# Power_Supply.net
KiCad netlist of a schematic drawn in Altium Designer
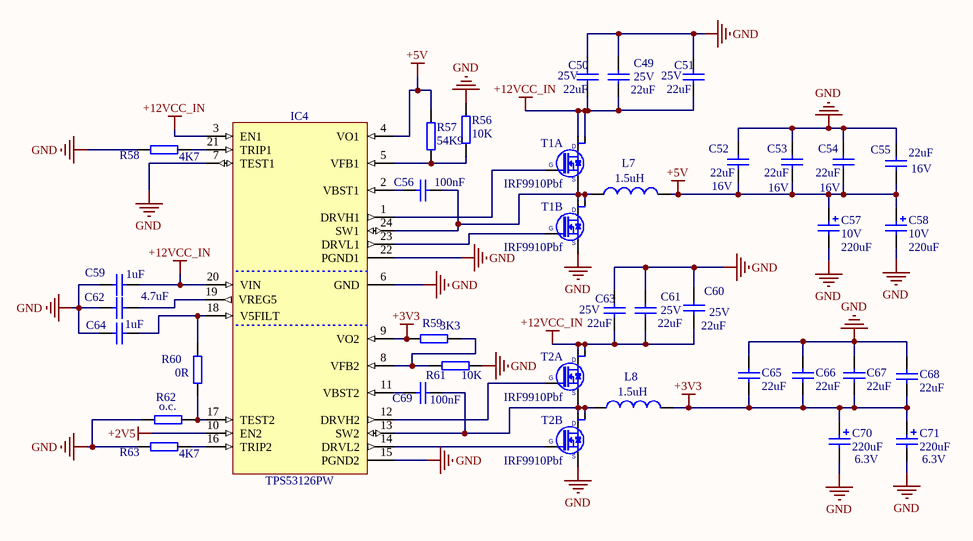
[diagram p0: Power_Supply.SchDoc]

(export (version "E")
  (design (tool "Eeschema 10.0.6"))
  (components
    (comp (ref "C49")
      (value "22uF")
      (footprint "CC3216-1206")
      (description "Capacitor")
      (fields
        (field (name "TOLERANCE") "±10%")
        (field (name "VOLTAGE") "25V")
        (field (name "Comment") "22uF 25V")
        (field (name "PUBLISHER") "Altium Limited")
      )
      (libsource (lib "wr_switch") (part "Cap"))
    )
    (comp (ref "C50")
      (value "22uF")
      (footprint "CC3216-1206")
      (description "Capacitor")
      (fields
        (field (name "TOLERANCE") "±10%")
        (field (name "VOLTAGE") "25V")
        (field (name "Comment") "22uF 25V")
        (field (name "PUBLISHER") "Altium Limited")
      )
      (libsource (lib "wr_switch") (part "Cap"))
    )
    (comp (ref "C51")
      (value "22uF")
      (footprint "CC3216-1206")
      (description "Capacitor")
      (fields
        (field (name "TOLERANCE") "±10%")
        (field (name "VOLTAGE") "25V")
        (field (name "Comment") "22uF 25V")
        (field (name "PUBLISHER") "Altium Limited")
      )
      (libsource (lib "wr_switch") (part "Cap"))
    )
    (comp (ref "C52")
      (value "22uF")
      (footprint "CC2012-0805")
      (description "Capacitor")
      (fields
        (field (name "TOLERANCE") "±10%")
        (field (name "VOLTAGE") "16V")
        (field (name "Comment") "22uF 16V")
        (field (name "PUBLISHER") "Altium Limited")
      )
      (libsource (lib "wr_switch") (part "Cap"))
    )
    (comp (ref "C53")
      (value "22uF")
      (footprint "CC2012-0805")
      (description "Capacitor")
      (fields
        (field (name "TOLERANCE") "±10%")
        (field (name "VOLTAGE") "16V")
        (field (name "Comment") "22uF 16V")
        (field (name "PUBLISHER") "Altium Limited")
      )
      (libsource (lib "wr_switch") (part "Cap"))
    )
    (comp (ref "C54")
      (value "22uF")
      (footprint "CC2012-0805")
      (description "Capacitor")
      (fields
        (field (name "TOLERANCE") "±10%")
        (field (name "VOLTAGE") "16V")
        (field (name "Comment") "22uF 16V")
        (field (name "PUBLISHER") "Altium Limited")
      )
      (libsource (lib "wr_switch") (part "Cap"))
    )
    (comp (ref "C55")
      (value "22uF")
      (footprint "CC2012-0805")
      (description "Capacitor")
      (fields
        (field (name "TOLERANCE") "±10%")
        (field (name "VOLTAGE") "16V")
        (field (name "Comment") "22uF 16V")
        (field (name "PUBLISHER") "Altium Limited")
      )
      (libsource (lib "wr_switch") (part "Cap"))
    )
    (comp (ref "C56")
      (value "100nF")
      (footprint "CC1005-0402")
      (description "Capacitor")
      (fields
        (field (name "TOLERANCE") "±10%")
        (field (name "VOLTAGE") "16V")
        (field (name "PUBLISHER") "Altium Limited")
      )
      (libsource (lib "wr_switch") (part "Cap"))
    )
    (comp (ref "C57")
      (value "220uF")
      (footprint "D")
      (description "Polarized Capacitor Tantalum")
      (fields
        (field (name "TOLERANCE") "±20%")
        (field (name "VOLTAGE") "10V")
        (field (name "Comment") "220uF 10V")
        (field (name "PUBLISHER") "Altium Limited")
      )
      (libsource (lib "wr_switch") (part "Cap Pol1"))
    )
    (comp (ref "C58")
      (value "220uF")
      (footprint "D")
      (description "Polarized Capacitor Tantalum")
      (fields
        (field (name "TOLERANCE") "±20%")
        (field (name "VOLTAGE") "10V")
        (field (name "Comment") "220uF 10V")
        (field (name "PUBLISHER") "Altium Limited")
      )
      (libsource (lib "wr_switch") (part "Cap Pol1"))
    )
    (comp (ref "C59")
      (value "1uF")
      (footprint "CC1608-0603")
      (description "Capacitor")
      (fields
        (field (name "TOLERANCE") "±10%")
        (field (name "VOLTAGE") "25V")
        (field (name "PUBLISHER") "Altium Limited")
      )
      (libsource (lib "wr_switch") (part "Cap"))
    )
    (comp (ref "C60")
      (value "22uF")
      (footprint "CC3216-1206")
      (description "Capacitor")
      (fields
        (field (name "TOLERANCE") "±10%")
        (field (name "VOLTAGE") "25V")
        (field (name "Comment") "22uF 25V")
        (field (name "PUBLISHER") "Altium Limited")
      )
      (libsource (lib "wr_switch") (part "Cap"))
    )
    (comp (ref "C61")
      (value "22uF")
      (footprint "CC3216-1206")
      (description "Capacitor")
      (fields
        (field (name "TOLERANCE") "±10%")
        (field (name "VOLTAGE") "25V")
        (field (name "Comment") "22uF 25V")
        (field (name "PUBLISHER") "Altium Limited")
      )
      (libsource (lib "wr_switch") (part "Cap"))
    )
    (comp (ref "C62")
      (value "4.7uF")
      (footprint "CC1608-0603")
      (description "Capacitor")
      (fields
        (field (name "TOLERANCE") "±10%")
        (field (name "VOLTAGE") "10V")
        (field (name "PUBLISHER") "Altium Limited")
      )
      (libsource (lib "wr_switch") (part "Cap"))
    )
    (comp (ref "C63")
      (value "22uF")
      (footprint "CC3216-1206")
      (description "Capacitor")
      (fields
        (field (name "TOLERANCE") "±10%")
        (field (name "VOLTAGE") "25V")
        (field (name "Comment") "22uF 25V")
        (field (name "PUBLISHER") "Altium Limited")
      )
      (libsource (lib "wr_switch") (part "Cap"))
    )
    (comp (ref "C64")
      (value "1uF")
      (footprint "CC1005-0402")
      (description "Capacitor")
      (fields
        (field (name "TOLERANCE") "±10%")
        (field (name "VOLTAGE") "16V")
        (field (name "PUBLISHER") "Altium Limited")
      )
      (libsource (lib "wr_switch") (part "Cap"))
    )
    (comp (ref "C65")
      (value "22uF")
      (footprint "CC2012-0805")
      (description "Capacitor")
      (fields
        (field (name "TOLERANCE") "±20%")
        (field (name "VOLTAGE") "6.3V")
        (field (name "PUBLISHER") "Altium Limited")
      )
      (libsource (lib "wr_switch") (part "Cap"))
    )
    (comp (ref "C66")
      (value "22uF")
      (footprint "CC2012-0805")
      (description "Capacitor")
      (fields
        (field (name "TOLERANCE") "±20%")
        (field (name "VOLTAGE") "6.3V")
        (field (name "PUBLISHER") "Altium Limited")
      )
      (libsource (lib "wr_switch") (part "Cap"))
    )
    (comp (ref "C67")
      (value "22uF")
      (footprint "CC2012-0805")
      (description "Capacitor")
      (fields
        (field (name "TOLERANCE") "±20%")
        (field (name "VOLTAGE") "6.3V")
        (field (name "PUBLISHER") "Altium Limited")
      )
      (libsource (lib "wr_switch") (part "Cap"))
    )
    (comp (ref "C68")
      (value "22uF")
      (footprint "CC2012-0805")
      (description "Capacitor")
      (fields
        (field (name "TOLERANCE") "±20%")
        (field (name "VOLTAGE") "6.3V")
        (field (name "PUBLISHER") "Altium Limited")
      )
      (libsource (lib "wr_switch") (part "Cap"))
    )
    (comp (ref "C69")
      (value "100nF")
      (footprint "CC1005-0402")
      (description "Capacitor")
      (fields
        (field (name "TOLERANCE") "±10%")
        (field (name "VOLTAGE") "16V")
        (field (name "PUBLISHER") "Altium Limited")
      )
      (libsource (lib "wr_switch") (part "Cap"))
    )
    (comp (ref "C70")
      (value "220uF")
      (footprint "D")
      (description "Polarized Capacitor Tantalum")
      (fields
        (field (name "TOLERANCE") "±20%")
        (field (name "VOLTAGE") "6.3V")
        (field (name "PUBLISHER") "Altium Limited")
      )
      (libsource (lib "wr_switch") (part "Cap Pol1"))
    )
    (comp (ref "C71")
      (value "220uF")
      (footprint "D")
      (description "Polarized Capacitor Tantalum")
      (fields
        (field (name "TOLERANCE") "±20%")
        (field (name "VOLTAGE") "6.3V")
        (field (name "PUBLISHER") "Altium Limited")
      )
      (libsource (lib "wr_switch") (part "Cap Pol1"))
    )
    (comp (ref "IC4")
      (value "TPS53126PW")
      (footprint "SOP65P640X120-24N")
      (description "Dual Synchronous Step-Down Controller For Low Voltage Power Rails")
      (fields (field (name "MANUFACTURER") "TEXAS INSTRUMENTS") (field (name "AUTHOR") "CERN DEM JLC"))
      (libsource (lib "wr_switch") (part "TPS53126PW"))
    )
    (comp (ref "L7")
      (value "1.5uH")
      (footprint "IHLP2525")
      (description "Low Profile, High Current Inductor")
      (fields
        (field (name "MANUFACTURER") "Vishay/Dale")
        (field (name "Comment") "IHLP2525CZER1R5M01")
        (field (name "PUBLISHER") "Altium Limited")
      )
      (libsource (lib "Miscellaneous Devices") (part "Inductor"))
    )
    (comp (ref "L8")
      (value "1.5uH")
      (footprint "IHLP2525")
      (description "Low Profile, High Current Inductor")
      (fields
        (field (name "MANUFACTURER") "Vishay/Dale")
        (field (name "Comment") "IHLP2525CZER1R5M01")
        (field (name "PUBLISHER") "Altium Limited")
      )
      (libsource (lib "Miscellaneous Devices") (part "Inductor"))
    )
    (comp (ref "R56")
      (value "10K")
      (footprint "0402")
      (description "SMD Resistor")
      (fields (field (name "TOLERANCE") "±1%"))
      (libsource (lib "wr_switch") (part "RES_SMD"))
    )
    (comp (ref "R57")
      (value "54K9")
      (footprint "0603")
      (description "SMD Resistor")
      (fields (field (name "TOLERANCE") "±1%"))
      (libsource (lib "wr_switch") (part "RES_SMD"))
    )
    (comp (ref "R58")
      (value "4K7")
      (footprint "0402")
      (description "SMD Resistor")
      (fields (field (name "TOLERANCE") "±1%"))
      (libsource (lib "wr_switch") (part "RES_SMD"))
    )
    (comp (ref "R59")
      (value "3K3")
      (footprint "0603")
      (description "SMD Resistor")
      (fields (field (name "TOLERANCE") "±1%"))
      (libsource (lib "wr_switch") (part "RES_SMD"))
    )
    (comp (ref "R60")
      (value "0R")
      (footprint "0402")
      (description "SMD Resistor")
      (fields (field (name "TOLERANCE") "Jumper"))
      (libsource (lib "wr_switch") (part "RES_SMD"))
    )
    (comp (ref "R61")
      (value "10K")
      (footprint "0402")
      (description "SMD Resistor")
      (fields (field (name "TOLERANCE") "±1%"))
      (libsource (lib "wr_switch") (part "RES_SMD"))
    )
    (comp (ref "R62")
      (value "o.c.")
      (footprint "0402")
      (description "SMD Resistor")
      (libsource (lib "wr_switch") (part "RES_SMD"))
    )
    (comp (ref "R63")
      (value "4K7")
      (footprint "0402")
      (description "SMD Resistor")
      (fields (field (name "TOLERANCE") "±1%"))
      (libsource (lib "wr_switch") (part "RES_SMD"))
    )
    (comp (ref "T1")
      (value "IRF9910Pbf")
      (footprint "SOIC127P600X175-8N")
      (description "Dual SO-8 MOSFET For POL Cconverter")
      (fields (field (name "MANUFACTURER") "INTERNATIONAL RECTIFIER") (field (name "AUTHOR") "CERN DEM JLC"))
      (libsource (lib "ICs And Semiconductors") (part "IRF9910"))
    )
    (comp (ref "T2")
      (value "IRF9910Pbf")
      (footprint "SOIC127P600X175-8N")
      (description "Dual SO-8 MOSFET For POL Cconverter")
      (fields (field (name "MANUFACTURER") "INTERNATIONAL RECTIFIER") (field (name "AUTHOR") "CERN DEM JLC"))
      (libsource (lib "ICs And Semiconductors") (part "IRF9910"))
    )
  )
  (nets
    (net (code "1") (name "+2V5") (class "Default")
      (node (ref "IC4") (pin "10") (pinfunction "EN2_10") (pintype "input"))
    )
    (net (code "2") (name "+3V3") (class "Default")
      (node (ref "C65") (pin "2") (pinfunction "2_2") (pintype "passive"))
      (node (ref "C66") (pin "1") (pinfunction "1_1") (pintype "passive"))
      (node (ref "C67") (pin "1") (pinfunction "1_1") (pintype "passive"))
      (node (ref "C68") (pin "1") (pinfunction "1_1") (pintype "passive"))
      (node (ref "C70") (pin "1") (pinfunction "1_1") (pintype "passive"))
      (node (ref "C71") (pin "1") (pinfunction "1_1") (pintype "passive"))
      (node (ref "IC4") (pin "9") (pinfunction "VO2_9") (pintype "input"))
      (node (ref "L8") (pin "2") (pinfunction "2_2") (pintype "passive"))
      (node (ref "R59") (pin "1") (pinfunction "1_1") (pintype "passive"))
    )
    (net (code "3") (name "+5V") (class "Default")
      (node (ref "C52") (pin "1") (pinfunction "1_1") (pintype "passive"))
      (node (ref "C53") (pin "1") (pinfunction "1_1") (pintype "passive"))
      (node (ref "C54") (pin "1") (pinfunction "1_1") (pintype "passive"))
      (node (ref "C55") (pin "1") (pinfunction "1_1") (pintype "passive"))
      (node (ref "C57") (pin "1") (pinfunction "1_1") (pintype "passive"))
      (node (ref "C58") (pin "1") (pinfunction "1_1") (pintype "passive"))
      (node (ref "IC4") (pin "4") (pinfunction "VO1_4") (pintype "input"))
      (node (ref "L7") (pin "2") (pinfunction "2_2") (pintype "passive"))
      (node (ref "R57") (pin "2") (pinfunction "2_2") (pintype "passive"))
    )
    (net (code "4") (name "+12VCC_IN") (class "Default")
      (node (ref "C49") (pin "1") (pinfunction "1_1") (pintype "passive"))
      (node (ref "C50") (pin "1") (pinfunction "1_1") (pintype "passive"))
      (node (ref "C51") (pin "1") (pinfunction "1_1") (pintype "passive"))
      (node (ref "C59") (pin "2") (pinfunction "2_2") (pintype "passive"))
      (node (ref "C60") (pin "1") (pinfunction "1_1") (pintype "passive"))
      (node (ref "C61") (pin "1") (pinfunction "1_1") (pintype "passive"))
      (node (ref "C63") (pin "1") (pinfunction "1_1") (pintype "passive"))
      (node (ref "IC4") (pin "20") (pinfunction "VIN_20") (pintype "input"))
      (node (ref "IC4") (pin "3") (pinfunction "EN1_3") (pintype "input"))
      (node (ref "T1") (pin "5") (pinfunction "D_5") (pintype "passive"))
      (node (ref "T1") (pin "6") (pinfunction "D_6") (pintype "passive"))
      (node (ref "T2") (pin "5") (pinfunction "D_5") (pintype "passive"))
      (node (ref "T2") (pin "6") (pinfunction "D_6") (pintype "passive"))
    )
    (net (code "5") (name "GND") (class "Default")
      (node (ref "C49") (pin "2") (pinfunction "2_2") (pintype "passive"))
      (node (ref "C50") (pin "2") (pinfunction "2_2") (pintype "passive"))
      (node (ref "C51") (pin "2") (pinfunction "2_2") (pintype "passive"))
      (node (ref "C52") (pin "2") (pinfunction "2_2") (pintype "passive"))
      (node (ref "C53") (pin "2") (pinfunction "2_2") (pintype "passive"))
      (node (ref "C54") (pin "2") (pinfunction "2_2") (pintype "passive"))
      (node (ref "C55") (pin "2") (pinfunction "2_2") (pintype "passive"))
      (node (ref "C57") (pin "2") (pinfunction "2_2") (pintype "passive"))
      (node (ref "C58") (pin "2") (pinfunction "2_2") (pintype "passive"))
      (node (ref "C59") (pin "1") (pinfunction "1_1") (pintype "passive"))
      (node (ref "C60") (pin "2") (pinfunction "2_2") (pintype "passive"))
      (node (ref "C61") (pin "2") (pinfunction "2_2") (pintype "passive"))
      (node (ref "C62") (pin "2") (pinfunction "2_2") (pintype "passive"))
      (node (ref "C63") (pin "2") (pinfunction "2_2") (pintype "passive"))
      (node (ref "C64") (pin "1") (pinfunction "1_1") (pintype "passive"))
      (node (ref "C65") (pin "1") (pinfunction "1_1") (pintype "passive"))
      (node (ref "C66") (pin "2") (pinfunction "2_2") (pintype "passive"))
      (node (ref "C67") (pin "2") (pinfunction "2_2") (pintype "passive"))
      (node (ref "C68") (pin "2") (pinfunction "2_2") (pintype "passive"))
      (node (ref "C70") (pin "2") (pinfunction "2_2") (pintype "passive"))
      (node (ref "C71") (pin "2") (pinfunction "2_2") (pintype "passive"))
      (node (ref "IC4") (pin "15") (pinfunction "PGND2_15") (pintype "power_in"))
      (node (ref "IC4") (pin "22") (pinfunction "PGND1_22") (pintype "power_in"))
      (node (ref "IC4") (pin "6") (pinfunction "GND_6") (pintype "power_in"))
      (node (ref "IC4") (pin "7") (pinfunction "TEST1_7") (pintype "bidirectional"))
      (node (ref "R56") (pin "2") (pinfunction "2_2") (pintype "passive"))
      (node (ref "R58") (pin "2") (pinfunction "2_2") (pintype "passive"))
      (node (ref "R61") (pin "2") (pinfunction "2_2") (pintype "passive"))
      (node (ref "R62") (pin "1") (pinfunction "1_1") (pintype "passive"))
      (node (ref "R63") (pin "2") (pinfunction "2_2") (pintype "passive"))
      (node (ref "T1") (pin "1") (pinfunction "S_1") (pintype "passive"))
      (node (ref "T2") (pin "1") (pinfunction "S_1") (pintype "passive"))
    )
    (net (code "6") (name "Net-(IC4-DRVH1)") (class "Default")
      (node (ref "IC4") (pin "1") (pinfunction "DRVH1_1") (pintype "output"))
      (node (ref "T1") (pin "4") (pinfunction "G_4") (pintype "passive"))
    )
    (net (code "7") (name "Net-(IC4-DRVH2)") (class "Default")
      (node (ref "IC4") (pin "12") (pinfunction "DRVH2_12") (pintype "output"))
      (node (ref "T2") (pin "4") (pinfunction "G_4") (pintype "passive"))
    )
    (net (code "8") (name "Net-(IC4-DRVL1)") (class "Default")
      (node (ref "IC4") (pin "23") (pinfunction "DRVL1_23") (pintype "output"))
      (node (ref "T1") (pin "2") (pinfunction "G_2") (pintype "passive"))
    )
    (net (code "9") (name "Net-(IC4-DRVL2)") (class "Default")
      (node (ref "IC4") (pin "14") (pinfunction "DRVL2_14") (pintype "output"))
      (node (ref "T2") (pin "2") (pinfunction "G_2") (pintype "passive"))
    )
    (net (code "10") (name "Net-(IC4-SW1)") (class "Default")
      (node (ref "C56") (pin "2") (pinfunction "2_2") (pintype "passive"))
      (node (ref "IC4") (pin "24") (pinfunction "SW1_24") (pintype "bidirectional"))
      (node (ref "L7") (pin "1") (pinfunction "1_1") (pintype "passive"))
      (node (ref "T1") (pin "3") (pinfunction "S_3") (pintype "passive"))
      (node (ref "T1") (pin "7") (pinfunction "D_7") (pintype "passive"))
      (node (ref "T1") (pin "8") (pinfunction "D_8") (pintype "passive"))
    )
    (net (code "11") (name "Net-(IC4-SW2)") (class "Default")
      (node (ref "C69") (pin "2") (pinfunction "2_2") (pintype "passive"))
      (node (ref "IC4") (pin "13") (pinfunction "SW2_13") (pintype "bidirectional"))
      (node (ref "L8") (pin "1") (pinfunction "1_1") (pintype "passive"))
      (node (ref "T2") (pin "3") (pinfunction "S_3") (pintype "passive"))
      (node (ref "T2") (pin "7") (pinfunction "D_7") (pintype "passive"))
      (node (ref "T2") (pin "8") (pinfunction "D_8") (pintype "passive"))
    )
    (net (code "12") (name "Net-(IC4-TEST2)") (class "Default")
      (node (ref "IC4") (pin "17") (pinfunction "TEST2_17") (pintype "input"))
      (node (ref "R60") (pin "2") (pinfunction "2_2") (pintype "passive"))
      (node (ref "R62") (pin "2") (pinfunction "2_2") (pintype "passive"))
    )
    (net (code "13") (name "Net-(IC4-TRIP1)") (class "Default")
      (node (ref "IC4") (pin "21") (pinfunction "TRIP1_21") (pintype "input"))
      (node (ref "R58") (pin "1") (pinfunction "1_1") (pintype "passive"))
    )
    (net (code "14") (name "Net-(IC4-TRIP2)") (class "Default")
      (node (ref "IC4") (pin "16") (pinfunction "TRIP2_16") (pintype "input"))
      (node (ref "R63") (pin "1") (pinfunction "1_1") (pintype "passive"))
    )
    (net (code "15") (name "Net-(IC4-V5FILT)") (class "Default")
      (node (ref "C64") (pin "2") (pinfunction "2_2") (pintype "passive"))
      (node (ref "IC4") (pin "18") (pinfunction "V5FILT_18") (pintype "input"))
      (node (ref "R60") (pin "1") (pinfunction "1_1") (pintype "passive"))
    )
    (net (code "16") (name "Net-(IC4-VBST1)") (class "Default")
      (node (ref "C56") (pin "1") (pinfunction "1_1") (pintype "passive"))
      (node (ref "IC4") (pin "2") (pinfunction "VBST1_2") (pintype "input"))
    )
    (net (code "17") (name "Net-(IC4-VBST2)") (class "Default")
      (node (ref "C69") (pin "1") (pinfunction "1_1") (pintype "passive"))
      (node (ref "IC4") (pin "11") (pinfunction "VBST2_11") (pintype "input"))
    )
    (net (code "18") (name "Net-(IC4-VFB1)") (class "Default")
      (node (ref "IC4") (pin "5") (pinfunction "VFB1_5") (pintype "input"))
      (node (ref "R56") (pin "1") (pinfunction "1_1") (pintype "passive"))
      (node (ref "R57") (pin "1") (pinfunction "1_1") (pintype "passive"))
    )
    (net (code "19") (name "Net-(IC4-VFB2)") (class "Default")
      (node (ref "IC4") (pin "8") (pinfunction "VFB2_8") (pintype "input"))
      (node (ref "R59") (pin "2") (pinfunction "2_2") (pintype "passive"))
      (node (ref "R61") (pin "1") (pinfunction "1_1") (pintype "passive"))
    )
    (net (code "20") (name "Net-(IC4-VREG5)") (class "Default")
      (node (ref "C62") (pin "1") (pinfunction "1_1") (pintype "passive"))
      (node (ref "IC4") (pin "19") (pinfunction "VREG5_19") (pintype "output"))
    )
  )
)
